# Sheet1.net
KiCad netlist of a schematic drawn in Altium Designer
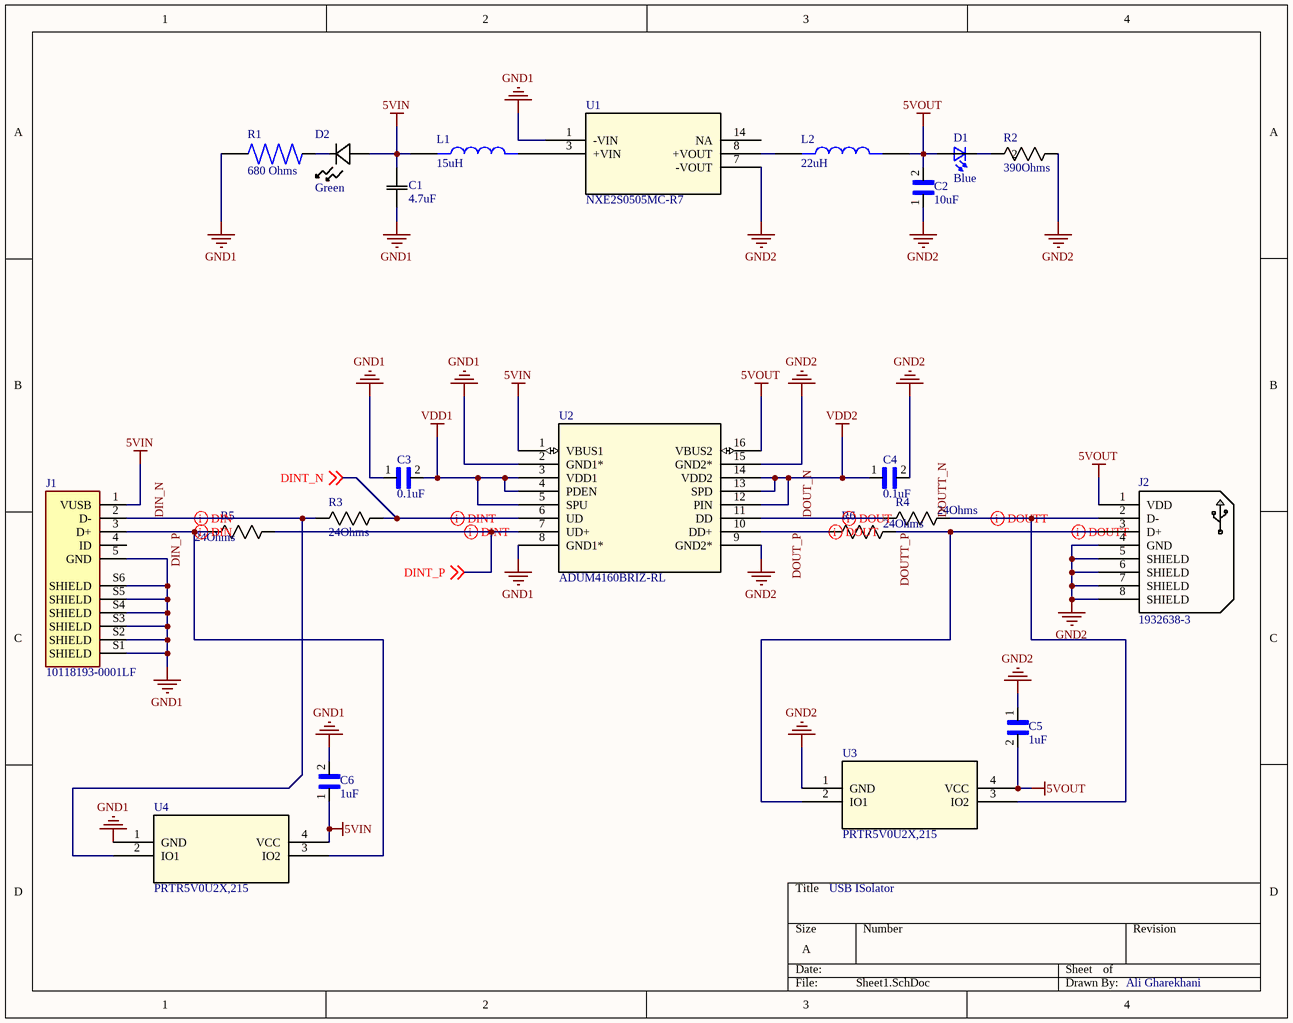
[diagram p0: Sheet1.SchDoc]

(export (version "E")
  (design (tool "Eeschema 10.0.6"))
  (components
    (comp (ref "C1")
      (value "4.7uF")
      (footprint "CAP_CL31_SAM")
      (description "No Description Available")
      (libsource (lib "CL31B475KOHNNNE") (part "CL31B475KOHNNNE"))
    )
    (comp (ref "C2")
      (value "10uF")
      (footprint "CAPC3216X140N")
      (fields (field (name "MP") "CL31B106MOHNNNE"))
      (libsource (lib "CL31B106MOHNNNE") (part "CL31B106MOHNNNE"))
    )
    (comp (ref "C3")
      (value "0.1uF")
      (footprint "CL10B104KB8NNNL:CAPC1608X90N")
      (description "0.1ÂµF Â±10% 50V Ceramic Capacitor X7R 0603 _1608 Metric_")
      (fields (field (name "MP") "CL10B104KB8NNNL") (field (name "MF") "Samsung Electro-Mechanics"))
      (libsource (lib "CL10B104KB8NNNL") (part "CL10B104KB8NNNL"))
    )
    (comp (ref "C4")
      (value "0.1uF")
      (footprint "CL10B104KB8NNNL:CAPC1608X90N")
      (description "0.1ÂµF Â±10% 50V Ceramic Capacitor X7R 0603 _1608 Metric_")
      (fields (field (name "MP") "CL10B104KB8NNNL") (field (name "MF") "Samsung Electro-Mechanics"))
      (libsource (lib "CL10B104KB8NNNL") (part "CL10B104KB8NNNL"))
    )
    (comp (ref "C5")
      (value "1uF")
      (footprint "CC0603KRX5R8BB105:CAPC1608X90")
      (fields (field (name "MF") "Yageo") (field (name "MP") "CC0603KRX5R8BB105"))
      (libsource (lib "") (part "CC0603KRX5R8BB105_1"))
    )
    (comp (ref "C6")
      (value "1uF")
      (footprint "CC0603KRX5R8BB105:CAPC1608X90")
      (fields (field (name "MF") "Yageo") (field (name "MP") "CC0603KRX5R8BB105"))
      (libsource (lib "CC0603KRX5R8BB105") (part "CC0603KRX5R8BB105"))
    )
    (comp (ref "D1")
      (value "Blue")
      (footprint "LTST-C194TBKT:0603")
      (description "Blue 468nm LED Indication - Discrete 3.3V 0603 _1608 Metric_")
      (fields (field (name "MF") "Lite-On Inc.") (field (name "DIGI-KEY_PART_NUMBER") "160-1837-1-ND"))
      (libsource (lib "LTST-C194TBKT") (part "LTST-C194TBKT"))
    )
    (comp (ref "D2")
      (value "Green")
      (footprint "LED_LTST-C191KGKT_LTO")
      (description "No Description Available")
      (libsource (lib "LTST-C191KGKT") (part "LTST-C191KGKT"))
    )
    (comp (ref "J1")
      (value "10118193-0001LF")
      (footprint "AMPHENOL_10118193-0001LF")
      (description "Micro USB 2.0, Input Output Connectors, B TYPE RECEPTACLE")
      (fields (field (name "MF") "Amphenol ICC"))
      (libsource (lib "10118193-0001LF") (part "10118193-0001LF"))
    )
    (comp (ref "J2")
      (value "1932638-3")
      (footprint "CONN4_1932638-3_TEC")
      (description "No Description Available")
      (libsource (lib "1932638-3") (part "1932638-3"))
    )
    (comp (ref "L1")
      (value "15uH")
      (footprint "IND_VLCF4028T-150MR88-2")
      (fields (field (name "MF") "TDK") (field (name "MP") "VLCF4028T-150MR88-2"))
      (libsource (lib "VLCF4028T-150MR88-2") (part "VLCF4028T-150MR88-2"))
    )
    (comp (ref "L2")
      (value "22uH")
      (footprint "IND_VLCF4024T-220MR65-2")
      (fields
        (field (name "MF") "{'manufacturer': u'TDK Corporation'}")
        (field (name "MP") "VLCF4024T-220MR65-2")
      )
      (libsource (lib "VLCF4024T-220MR65-2") (part "VLCF4024T-220MR65-2"))
    )
    (comp (ref "R1")
      (value "680 Ohms")
      (footprint "RESC1608X55N:RESC1608X55N")
      (description "Res Thick Film 0603 680 Ohm 5% 1/10W Â±200ppm/Â°C Molded SMD SMD Paper Tape on Plastic Reel")
      (fields (field (name "MP") "CR0603-JW-681ELF"))
      (libsource (lib "CR0603-JW-681ELF") (part "CR0603-JW-681ELF"))
    )
    (comp (ref "R2")
      (value "390Ohms")
      (footprint "RES_CRCW_0603")
      (description "No Description Available")
      (libsource (lib "CRCW0603390RFKEA") (part "CRCW0603390RFKEA"))
    )
    (comp (ref "R3")
      (value "24Ohms")
      (footprint "RES_CRCW_0603")
      (description "No Description Available")
      (libsource (lib "CRCW060324R0FKEA") (part "CRCW060324R0FKEA"))
    )
    (comp (ref "R4")
      (value "24Ohms")
      (footprint "RES_CRCW_0603")
      (description "No Description Available")
      (libsource (lib "CRCW060324R0FKEA") (part "CRCW060324R0FKEA"))
    )
    (comp (ref "R5")
      (value "24Ohms")
      (footprint "RES_CRCW_0603")
      (description "No Description Available")
      (libsource (lib "CRCW060324R0FKEA") (part "CRCW060324R0FKEA"))
    )
    (comp (ref "R6")
      (value "24Ohms")
      (footprint "RES_CRCW_0603")
      (description "No Description Available")
      (libsource (lib "CRCW060324R0FKEA") (part "CRCW060324R0FKEA"))
    )
    (comp (ref "U1")
      (value "NXE2S0505MC-R7")
      (footprint "NXE2_SINGLE_SURFACE_MUR")
      (description "No Description Available")
      (libsource (lib "NXE2S0505MC-R7") (part "NXE2S0505MC-R7"))
    )
    (comp (ref "U2")
      (value "ADUM4160BRIZ-RL")
      (footprint "RI_16_2_ADI")
      (description "No Description Available")
      (libsource (lib "ADUM4160BRIZ-RL") (part "ADUM4160BRIZ-RL"))
    )
    (comp (ref "U3")
      (value "PRTR5V0U2X,215")
      (footprint "SOT143B_PRTR5V0U2X,215_NEX")
      (description "No Description Available")
      (libsource (lib "PRTR5V0U2X,215") (part "PRTR5V0U2X,215"))
    )
    (comp (ref "U4")
      (value "PRTR5V0U2X,215")
      (footprint "SOT143B_PRTR5V0U2X,215_NEX")
      (description "No Description Available")
      (libsource (lib "PRTR5V0U2X,215") (part "PRTR5V0U2X,215"))
    )
  )
  (nets
    (net (code "1") (name "/DIN_N") (class "Default")
      (node (ref "J1") (pin "2") (pinfunction "D-_2") (pintype "passive"))
      (node (ref "R3") (pin "2") (pinfunction "2_2") (pintype "passive"))
      (node (ref "U4") (pin "2") (pinfunction "IO1_2") (pintype "passive"))
    )
    (net (code "2") (name "/DIN_P") (class "Default")
      (node (ref "J1") (pin "3") (pinfunction "D+_3") (pintype "passive"))
      (node (ref "R5") (pin "2") (pinfunction "2_2") (pintype "passive"))
      (node (ref "U4") (pin "3") (pinfunction "IO2_3") (pintype "passive"))
    )
    (net (code "3") (name "/DOUTT_N") (class "Default")
      (node (ref "J2") (pin "2") (pinfunction "D-_2") (pintype "passive"))
      (node (ref "R4") (pin "1") (pinfunction "1_1") (pintype "passive"))
      (node (ref "U3") (pin "3") (pinfunction "IO2_3") (pintype "passive"))
    )
    (net (code "4") (name "/DOUTT_P") (class "Default")
      (node (ref "J2") (pin "3") (pinfunction "D+_3") (pintype "passive"))
      (node (ref "R6") (pin "1") (pinfunction "1_1") (pintype "passive"))
      (node (ref "U3") (pin "2") (pinfunction "IO1_2") (pintype "passive"))
    )
    (net (code "5") (name "/DOUT_N") (class "Default")
      (node (ref "R4") (pin "2") (pinfunction "2_2") (pintype "passive"))
      (node (ref "U2") (pin "11") (pinfunction "DD_11") (pintype "passive"))
    )
    (net (code "6") (name "/DOUT_P") (class "Default")
      (node (ref "R6") (pin "2") (pinfunction "2_2") (pintype "passive"))
      (node (ref "U2") (pin "10") (pinfunction "DD+_10") (pintype "passive"))
    )
    (net (code "7") (name "5VIN") (class "Default")
      (node (ref "C1") (pin "2") (pinfunction "2_2") (pintype "passive"))
      (node (ref "C6") (pin "1") (pinfunction "1_1") (pintype "passive"))
      (node (ref "D2") (pin "2") (pinfunction "ANODE_2") (pintype "passive"))
      (node (ref "J1") (pin "1") (pinfunction "VUSB_1") (pintype "passive"))
      (node (ref "L1") (pin "1") (pinfunction "1_1") (pintype "passive"))
      (node (ref "U2") (pin "1") (pinfunction "VBUS1_1") (pintype "bidirectional"))
      (node (ref "U4") (pin "4") (pinfunction "VCC_4") (pintype "passive"))
    )
    (net (code "8") (name "5VOUT") (class "Default")
      (node (ref "C2") (pin "2") (pinfunction "2_2") (pintype "passive"))
      (node (ref "C5") (pin "2") (pinfunction "2_2") (pintype "passive"))
      (node (ref "D1") (pin "2") (pinfunction "A2_2") (pintype "passive"))
      (node (ref "J2") (pin "1") (pinfunction "VDD_1") (pintype "passive"))
      (node (ref "L2") (pin "2") (pinfunction "2_2") (pintype "passive"))
      (node (ref "U2") (pin "16") (pinfunction "VBUS2_16") (pintype "bidirectional"))
      (node (ref "U3") (pin "4") (pinfunction "VCC_4") (pintype "passive"))
    )
    (net (code "9") (name "DINT_N") (class "Default")
      (node (ref "R3") (pin "1") (pinfunction "1_1") (pintype "passive"))
      (node (ref "U2") (pin "6") (pinfunction "UD_6") (pintype "passive"))
    )
    (net (code "10") (name "DINT_P") (class "Default")
      (node (ref "R5") (pin "1") (pinfunction "1_1") (pintype "passive"))
      (node (ref "U2") (pin "7") (pinfunction "UD+_7") (pintype "passive"))
    )
    (net (code "11") (name "GND1") (class "Default")
      (node (ref "C1") (pin "1") (pinfunction "1_1") (pintype "passive"))
      (node (ref "C3") (pin "1") (pinfunction "1_1") (pintype "passive"))
      (node (ref "C6") (pin "2") (pinfunction "2_2") (pintype "passive"))
      (node (ref "J1") (pin "5") (pinfunction "GND_5") (pintype "passive"))
      (node (ref "J1") (pin "S1") (pinfunction "SHIELD_S1") (pintype "passive"))
      (node (ref "J1") (pin "S2") (pinfunction "SHIELD_S2") (pintype "passive"))
      (node (ref "J1") (pin "S3") (pinfunction "SHIELD_S3") (pintype "passive"))
      (node (ref "J1") (pin "S4") (pinfunction "SHIELD_S4") (pintype "passive"))
      (node (ref "J1") (pin "S5") (pinfunction "SHIELD_S5") (pintype "passive"))
      (node (ref "J1") (pin "S6") (pinfunction "SHIELD_S6") (pintype "passive"))
      (node (ref "R1") (pin "1") (pinfunction "1_1") (pintype "passive"))
      (node (ref "U1") (pin "1") (pinfunction "-VIN_1") (pintype "power_in"))
      (node (ref "U2") (pin "2") (pinfunction "GND1*_2") (pintype "power_in"))
      (node (ref "U2") (pin "8") (pinfunction "GND1*_8") (pintype "power_in"))
      (node (ref "U4") (pin "1") (pinfunction "GND_1") (pintype "passive"))
    )
    (net (code "12") (name "GND2") (class "Default")
      (node (ref "C2") (pin "1") (pinfunction "1_1") (pintype "passive"))
      (node (ref "C4") (pin "2") (pinfunction "2_2") (pintype "passive"))
      (node (ref "C5") (pin "1") (pinfunction "1_1") (pintype "passive"))
      (node (ref "J2") (pin "4") (pinfunction "GND_4") (pintype "passive"))
      (node (ref "J2") (pin "5") (pinfunction "SHIELD_5") (pintype "passive"))
      (node (ref "J2") (pin "6") (pinfunction "SHIELD_6") (pintype "passive"))
      (node (ref "J2") (pin "7") (pinfunction "SHIELD_7") (pintype "passive"))
      (node (ref "J2") (pin "8") (pinfunction "SHIELD_8") (pintype "passive"))
      (node (ref "R2") (pin "1") (pinfunction "1_1") (pintype "passive"))
      (node (ref "U1") (pin "7") (pinfunction "-VOUT_7") (pintype "passive"))
      (node (ref "U2") (pin "15") (pinfunction "GND2*_15") (pintype "power_in"))
      (node (ref "U2") (pin "9") (pinfunction "GND2*_9") (pintype "power_in"))
      (node (ref "U3") (pin "1") (pinfunction "GND_1") (pintype "passive"))
    )
    (net (code "13") (name "Net-(D1-K2)") (class "Default")
      (node (ref "D1") (pin "1") (pinfunction "K2_1") (pintype "passive"))
      (node (ref "R2") (pin "2") (pinfunction "2_2") (pintype "passive"))
    )
    (net (code "14") (name "Net-(D2-CATHODE)") (class "Default")
      (node (ref "D2") (pin "1") (pinfunction "CATHODE_1") (pintype "passive"))
      (node (ref "R1") (pin "2") (pinfunction "2_2") (pintype "passive"))
    )
    (net (code "15") (name "Net-(U1-+VIN)") (class "Default")
      (node (ref "L1") (pin "2") (pinfunction "2_2") (pintype "passive"))
      (node (ref "U1") (pin "3") (pinfunction "+VIN_3") (pintype "power_in"))
    )
    (net (code "16") (name "Net-(U1-+VOUT)") (class "Default")
      (node (ref "L2") (pin "1") (pinfunction "1_1") (pintype "passive"))
      (node (ref "U1") (pin "8") (pinfunction "+VOUT_8") (pintype "passive"))
    )
    (net (code "17") (name "VDD1") (class "Default")
      (node (ref "C3") (pin "2") (pinfunction "2_2") (pintype "passive"))
      (node (ref "U2") (pin "3") (pinfunction "VDD1_3") (pintype "power_in"))
      (node (ref "U2") (pin "4") (pinfunction "PDEN_4") (pintype "passive"))
      (node (ref "U2") (pin "5") (pinfunction "SPU_5") (pintype "passive"))
    )
    (net (code "18") (name "VDD2") (class "Default")
      (node (ref "C4") (pin "1") (pinfunction "1_1") (pintype "passive"))
      (node (ref "U2") (pin "12") (pinfunction "PIN_12") (pintype "passive"))
      (node (ref "U2") (pin "13") (pinfunction "SPD_13") (pintype "passive"))
      (node (ref "U2") (pin "14") (pinfunction "VDD2_14") (pintype "power_in"))
    )
    (net (code "19") (name "unconnected-(J1-ID-Pad4)") (class "Default")
      (node (ref "J1") (pin "4") (pinfunction "ID_4") (pintype "passive"))
    )
    (net (code "20") (name "unconnected-(U1-NA-Pad14)") (class "Default")
      (node (ref "U1") (pin "14") (pinfunction "NA_14") (pintype "passive"))
    )
  )
)
